# MCP4725.net
KiCad netlist of a schematic drawn in EAGLE
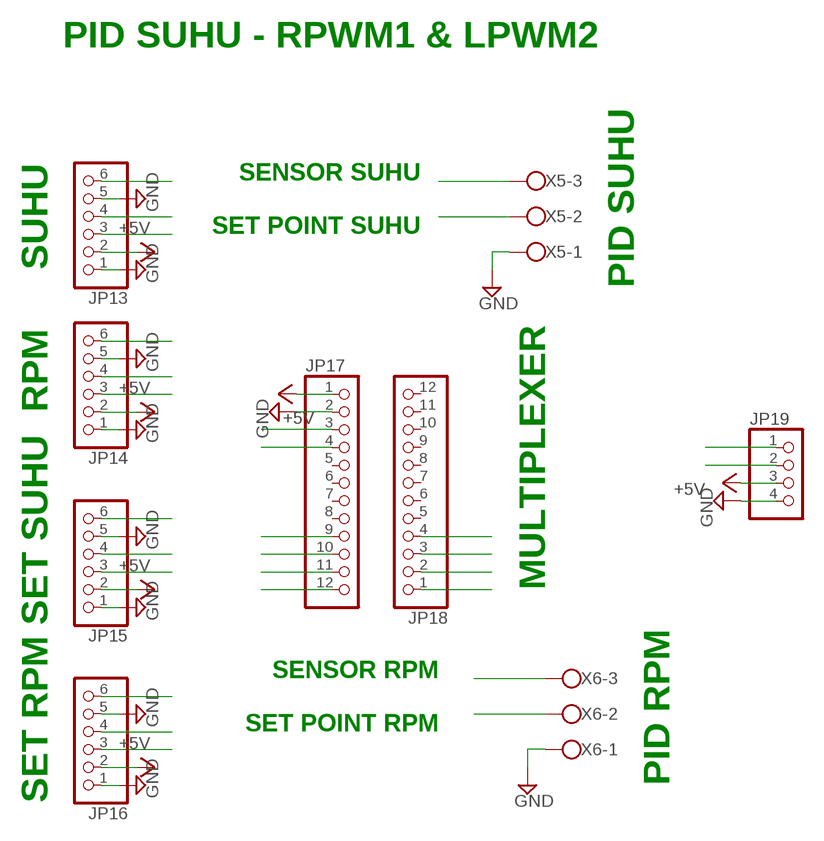
[diagram p0: schematic, sheet 1]

(export (version "E")
  (design (tool "Eeschema 10.0.6"))
  (components
    (comp (ref "JP13")
      (value "PINHD-1X6")
      (footprint "eagle-import:1X06")
      (libsource (lib "eagle-import") (part "PINHD-1X6"))
    )
    (comp (ref "JP14")
      (value "PINHD-1X6")
      (footprint "eagle-import:1X06")
      (libsource (lib "eagle-import") (part "PINHD-1X6"))
    )
    (comp (ref "JP15")
      (value "PINHD-1X6")
      (footprint "eagle-import:1X06")
      (libsource (lib "eagle-import") (part "PINHD-1X6"))
    )
    (comp (ref "JP16")
      (value "PINHD-1X6")
      (footprint "eagle-import:1X06")
      (libsource (lib "eagle-import") (part "PINHD-1X6"))
    )
    (comp (ref "JP17")
      (value "PINHD-1X12")
      (footprint "eagle-import:1X12")
      (libsource (lib "eagle-import") (part "PINHD-1X12"))
    )
    (comp (ref "JP18")
      (value "PINHD-1X12")
      (footprint "eagle-import:1X12")
      (libsource (lib "eagle-import") (part "PINHD-1X12"))
    )
    (comp (ref "JP19")
      (value "PINHD-1X4")
      (footprint "eagle-import:1X04")
      (libsource (lib "eagle-import") (part "PINHD-1X4"))
    )
    (comp (ref "X5")
      (value "W237-103")
      (footprint "eagle-import:W237-103")
      (fields (field (name "MPN") "237-103"))
      (libsource (lib "eagle-import") (part "W237-103"))
    )
    (comp (ref "X6")
      (value "W237-103")
      (footprint "eagle-import:W237-103")
      (fields (field (name "MPN") "237-103"))
      (libsource (lib "eagle-import") (part "W237-103"))
    )
  )
  (nets
    (net (code "1") (name "+5V") (class "Default")
      (node (ref "JP13") (pin "2") (pinfunction "2_2") (pintype "passive"))
      (node (ref "JP14") (pin "2") (pinfunction "2_2") (pintype "passive"))
      (node (ref "JP15") (pin "2") (pinfunction "2_2") (pintype "passive"))
      (node (ref "JP16") (pin "2") (pinfunction "2_2") (pintype "passive"))
      (node (ref "JP17") (pin "1") (pinfunction "1_1") (pintype "passive"))
      (node (ref "JP19") (pin "3") (pinfunction "3_3") (pintype "passive"))
    )
    (net (code "2") (name "/N$37") (class "Default")
      (node (ref "JP13") (pin "3") (pinfunction "3_3") (pintype "passive"))
      (node (ref "JP17") (pin "9") (pinfunction "9_9") (pintype "passive"))
    )
    (net (code "3") (name "/N$38") (class "Default")
      (node (ref "JP13") (pin "4") (pinfunction "4_4") (pintype "passive"))
      (node (ref "JP17") (pin "10") (pinfunction "10_10") (pintype "passive"))
    )
    (net (code "4") (name "/N$39") (class "Default")
      (node (ref "JP14") (pin "3") (pinfunction "3_3") (pintype "passive"))
      (node (ref "JP17") (pin "11") (pinfunction "11_11") (pintype "passive"))
    )
    (net (code "5") (name "/N$40") (class "Default")
      (node (ref "JP14") (pin "4") (pinfunction "4_4") (pintype "passive"))
      (node (ref "JP17") (pin "12") (pinfunction "12_12") (pintype "passive"))
    )
    (net (code "6") (name "/N$41") (class "Default")
      (node (ref "JP15") (pin "3") (pinfunction "3_3") (pintype "passive"))
      (node (ref "JP18") (pin "1") (pinfunction "1_1") (pintype "passive"))
    )
    (net (code "7") (name "/N$42") (class "Default")
      (node (ref "JP15") (pin "4") (pinfunction "4_4") (pintype "passive"))
      (node (ref "JP18") (pin "2") (pinfunction "2_2") (pintype "passive"))
    )
    (net (code "8") (name "/N$43") (class "Default")
      (node (ref "JP16") (pin "4") (pinfunction "4_4") (pintype "passive"))
      (node (ref "JP18") (pin "4") (pinfunction "4_4") (pintype "passive"))
    )
    (net (code "9") (name "/N$44") (class "Default")
      (node (ref "JP16") (pin "3") (pinfunction "3_3") (pintype "passive"))
      (node (ref "JP18") (pin "3") (pinfunction "3_3") (pintype "passive"))
    )
    (net (code "10") (name "/N$45") (class "Default")
      (node (ref "JP17") (pin "3") (pinfunction "3_3") (pintype "passive"))
      (node (ref "JP19") (pin "2") (pinfunction "2_2") (pintype "passive"))
    )
    (net (code "11") (name "/N$46") (class "Default")
      (node (ref "JP17") (pin "4") (pinfunction "4_4") (pintype "passive"))
      (node (ref "JP19") (pin "1") (pinfunction "1_1") (pintype "passive"))
    )
    (net (code "12") (name "/N$47") (class "Default")
      (node (ref "JP15") (pin "6") (pinfunction "6_6") (pintype "passive"))
      (node (ref "X5") (pin "2") (pinfunction "KL_2") (pintype "passive"))
    )
    (net (code "13") (name "/N$48") (class "Default")
      (node (ref "JP13") (pin "6") (pinfunction "6_6") (pintype "passive"))
      (node (ref "X5") (pin "3") (pinfunction "KL_3") (pintype "passive"))
    )
    (net (code "14") (name "/N$49") (class "Default")
      (node (ref "JP14") (pin "6") (pinfunction "6_6") (pintype "passive"))
      (node (ref "X6") (pin "3") (pinfunction "KL_3") (pintype "passive"))
    )
    (net (code "15") (name "/N$50") (class "Default")
      (node (ref "JP16") (pin "6") (pinfunction "6_6") (pintype "passive"))
      (node (ref "X6") (pin "2") (pinfunction "KL_2") (pintype "passive"))
    )
    (net (code "16") (name "GND") (class "Default")
      (node (ref "JP13") (pin "1") (pinfunction "1_1") (pintype "passive"))
      (node (ref "JP13") (pin "5") (pinfunction "5_5") (pintype "passive"))
      (node (ref "JP14") (pin "1") (pinfunction "1_1") (pintype "passive"))
      (node (ref "JP14") (pin "5") (pinfunction "5_5") (pintype "passive"))
      (node (ref "JP15") (pin "1") (pinfunction "1_1") (pintype "passive"))
      (node (ref "JP15") (pin "5") (pinfunction "5_5") (pintype "passive"))
      (node (ref "JP16") (pin "1") (pinfunction "1_1") (pintype "passive"))
      (node (ref "JP16") (pin "5") (pinfunction "5_5") (pintype "passive"))
      (node (ref "JP17") (pin "2") (pinfunction "2_2") (pintype "passive"))
      (node (ref "JP19") (pin "4") (pinfunction "4_4") (pintype "passive"))
      (node (ref "X5") (pin "1") (pinfunction "KL_1") (pintype "passive"))
      (node (ref "X6") (pin "1") (pinfunction "KL_1") (pintype "passive"))
    )
    (net (code "17") (name "unconnected-(JP17-Pad5)") (class "Default")
      (node (ref "JP17") (pin "5") (pinfunction "5_5") (pintype "passive"))
    )
    (net (code "18") (name "unconnected-(JP17-Pad6)") (class "Default")
      (node (ref "JP17") (pin "6") (pinfunction "6_6") (pintype "passive"))
    )
    (net (code "19") (name "unconnected-(JP17-Pad7)") (class "Default")
      (node (ref "JP17") (pin "7") (pinfunction "7_7") (pintype "passive"))
    )
    (net (code "20") (name "unconnected-(JP17-Pad8)") (class "Default")
      (node (ref "JP17") (pin "8") (pinfunction "8_8") (pintype "passive"))
    )
    (net (code "21") (name "unconnected-(JP18-Pad5)") (class "Default")
      (node (ref "JP18") (pin "5") (pinfunction "5_5") (pintype "passive"))
    )
    (net (code "22") (name "unconnected-(JP18-Pad6)") (class "Default")
      (node (ref "JP18") (pin "6") (pinfunction "6_6") (pintype "passive"))
    )
    (net (code "23") (name "unconnected-(JP18-Pad7)") (class "Default")
      (node (ref "JP18") (pin "7") (pinfunction "7_7") (pintype "passive"))
    )
    (net (code "24") (name "unconnected-(JP18-Pad8)") (class "Default")
      (node (ref "JP18") (pin "8") (pinfunction "8_8") (pintype "passive"))
    )
    (net (code "25") (name "unconnected-(JP18-Pad9)") (class "Default")
      (node (ref "JP18") (pin "9") (pinfunction "9_9") (pintype "passive"))
    )
    (net (code "26") (name "unconnected-(JP18-Pad10)") (class "Default")
      (node (ref "JP18") (pin "10") (pinfunction "10_10") (pintype "passive"))
    )
    (net (code "27") (name "unconnected-(JP18-Pad11)") (class "Default")
      (node (ref "JP18") (pin "11") (pinfunction "11_11") (pintype "passive"))
    )
    (net (code "28") (name "unconnected-(JP18-Pad12)") (class "Default")
      (node (ref "JP18") (pin "12") (pinfunction "12_12") (pintype "passive"))
    )
  )
)
